# LCD.net
KiCad netlist of a schematic drawn in Altium Designer
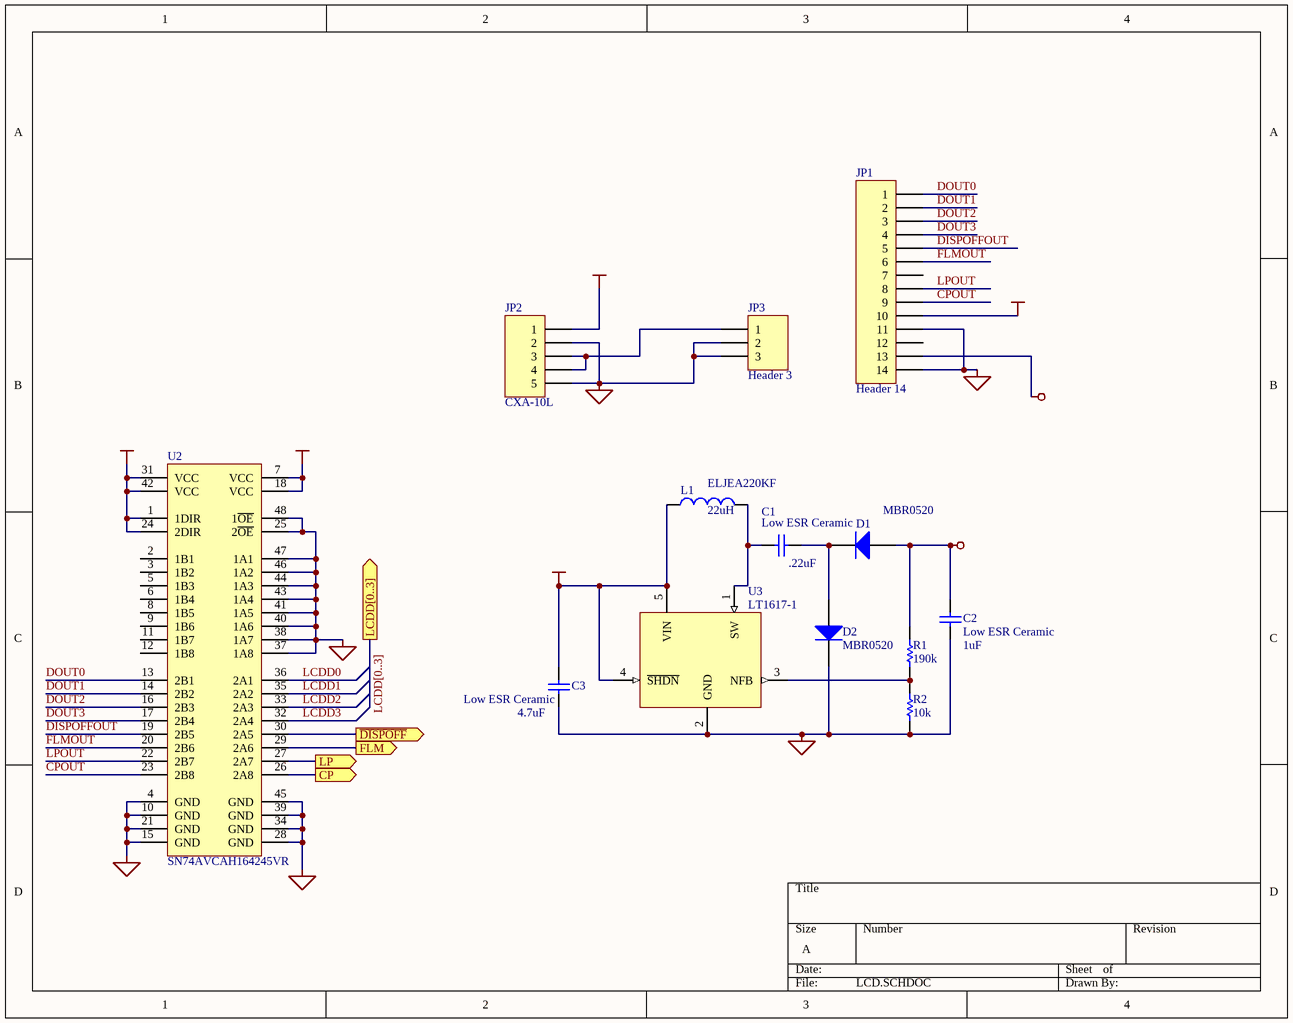
[diagram p0: LCD.SCHDOC]

(export (version "E")
  (design (tool "Eeschema 10.0.6"))
  (components
    (comp (ref "C1")
      (value "Low ESR Ceramic")
      (footprint "CC3216-1206")
      (description "Capacitor")
      (fields
        (field (name "MANUFACTURER") "Generic Components")
        (field (name "ALTIUM_VALUE") ".22uF")
        (field (name "PUBLISHER") "Altium Limited")
      )
      (libsource (lib "Miscellaneous Devices") (part "Cap"))
    )
    (comp (ref "C2")
      (value "Low ESR Ceramic")
      (footprint "CC3216-1206")
      (description "Capacitor")
      (fields
        (field (name "MANUFACTURER") "Generic Components")
        (field (name "ALTIUM_VALUE") "1uF")
        (field (name "PUBLISHER") "Altium Limited")
      )
      (libsource (lib "Miscellaneous Devices") (part "Cap"))
    )
    (comp (ref "C3")
      (value "Low ESR Ceramic")
      (footprint "CC3216-1206")
      (description "Capacitor")
      (fields
        (field (name "MANUFACTURER") "Generic Components")
        (field (name "ALTIUM_VALUE") "4.7uF")
        (field (name "PUBLISHER") "Altium Limited")
      )
      (libsource (lib "Miscellaneous Devices") (part "Cap"))
    )
    (comp (ref "D1")
      (value "MBR0520")
      (footprint "SOD-123")
      (description "Default Diode")
      (fields (field (name "MANUFACTURER") "Generic Components") (field (name "PUBLISHER") "Altium Limited"))
      (libsource (lib "Miscellaneous Devices") (part "Diode"))
    )
    (comp (ref "D2")
      (value "MBR0520")
      (footprint "SOD-123")
      (description "Default Diode")
      (fields (field (name "MANUFACTURER") "Generic Components") (field (name "PUBLISHER") "Altium Limited"))
      (libsource (lib "Miscellaneous Devices") (part "Diode"))
    )
    (comp (ref "JP1")
      (value "Header 14")
      (footprint "MOLEX FPC 14-CONN VERT")
      (description "Header, 14-Pin")
      (fields (field (name "MANUFACTURER") "Generic Components") (field (name "PUBLISHER") "Altium Limited"))
      (libsource (lib "Miscellaneous Connectors") (part "Header 14"))
    )
    (comp (ref "JP2")
      (value "CXA-10L")
      (footprint "CXA-L10L")
      (description "Header, 5-Pin")
      (fields (field (name "MANUFACTURER") "Generic Components") (field (name "PUBLISHER") "Altium Limited"))
      (libsource (lib "Miscellaneous Connectors") (part "Header 5"))
    )
    (comp (ref "JP3")
      (value "Header 3")
      (footprint "TERMBLOCK3.5x3")
      (description "Header, 3-Pin")
      (fields (field (name "MANUFACTURER") "Generic Components") (field (name "PUBLISHER") "Altium Limited"))
      (libsource (lib "Miscellaneous Connectors") (part "Header 3"))
    )
    (comp (ref "L1")
      (value "ELJEA220KF")
      (footprint "CC3225-1210")
      (description "Inductor")
      (fields
        (field (name "MANUFACTURER") "Generic Components")
        (field (name "ALTIUM_VALUE") "22uH")
        (field (name "PUBLISHER") "Altium Limited")
      )
      (libsource (lib "Miscellaneous Devices") (part "Inductor"))
    )
    (comp (ref "R1")
      (value "190k")
      (footprint "CC2012-0805")
      (description "Resistor")
      (fields
        (field (name "MANUFACTURER") "Generic Components")
        (field (name "Comment") "Res1")
        (field (name "PUBLISHER") "Altium Limited")
      )
      (libsource (lib "Miscellaneous Devices") (part "Res1"))
    )
    (comp (ref "R2")
      (value "10k")
      (footprint "CC2012-0805")
      (description "Resistor")
      (fields
        (field (name "MANUFACTURER") "Generic Components")
        (field (name "Comment") "Res1")
        (field (name "PUBLISHER") "Altium Limited")
      )
      (libsource (lib "Miscellaneous Devices") (part "Res1"))
    )
    (comp (ref "U2")
      (value "SN74AVCAH164245VR")
      (footprint "TSSO10x6-G48")
      (description "16-bit bus transceiver with 3-state outputs")
      (libsource (lib "My devices") (part "SN74LVCH16245A"))
    )
    (comp (ref "U3")
      (value "LT1617-1")
      (footprint "SO-G5/P.95")
      (description "Micropower Inverting DC/DC converter")
      (libsource (lib "My devices") (part "LT1617"))
    )
  )
  (nets
    (net (code "1") (name "+5VCC") (class "Default")
      (node (ref "JP1") (pin "10") (pinfunction "10_10") (pintype "passive"))
      (node (ref "JP2") (pin "1") (pinfunction "1_1") (pintype "passive"))
      (node (ref "U2") (pin "18") (pinfunction "VCC_18") (pintype "power_in"))
      (node (ref "U2") (pin "7") (pinfunction "VCC_7") (pintype "power_in"))
    )
    (net (code "2") (name "-25VEE") (class "Default")
      (node (ref "C2") (pin "2") (pinfunction "2_2") (pintype "passive"))
      (node (ref "D1") (pin "1") (pinfunction "A_1") (pintype "passive"))
      (node (ref "JP1") (pin "13") (pinfunction "13_13") (pintype "passive"))
      (node (ref "R1") (pin "2") (pinfunction "2_2") (pintype "passive"))
    )
    (net (code "3") (name "/CP") (class "Default")
      (node (ref "U2") (pin "26") (pinfunction "2A8_26") (pintype "passive"))
    )
    (net (code "4") (name "/CPOUT") (class "Default")
      (node (ref "JP1") (pin "9") (pinfunction "9_9") (pintype "passive"))
      (node (ref "U2") (pin "23") (pinfunction "2B8_23") (pintype "passive"))
    )
    (net (code "5") (name "/DISPOFFOUT") (class "Default")
      (node (ref "JP1") (pin "5") (pinfunction "5_5") (pintype "passive"))
      (node (ref "U2") (pin "19") (pinfunction "2B5_19") (pintype "passive"))
    )
    (net (code "6") (name "/DOUT0") (class "Default")
      (node (ref "JP1") (pin "1") (pinfunction "1_1") (pintype "passive"))
      (node (ref "U2") (pin "13") (pinfunction "2B1_13") (pintype "passive"))
    )
    (net (code "7") (name "/DOUT1") (class "Default")
      (node (ref "JP1") (pin "2") (pinfunction "2_2") (pintype "passive"))
      (node (ref "U2") (pin "14") (pinfunction "2B2_14") (pintype "passive"))
    )
    (net (code "8") (name "/DOUT2") (class "Default")
      (node (ref "JP1") (pin "3") (pinfunction "3_3") (pintype "passive"))
      (node (ref "U2") (pin "16") (pinfunction "2B3_16") (pintype "passive"))
    )
    (net (code "9") (name "/DOUT3") (class "Default")
      (node (ref "JP1") (pin "4") (pinfunction "4_4") (pintype "passive"))
      (node (ref "U2") (pin "17") (pinfunction "2B4_17") (pintype "passive"))
    )
    (net (code "10") (name "/FLM") (class "Default")
      (node (ref "U2") (pin "29") (pinfunction "2A6_29") (pintype "passive"))
    )
    (net (code "11") (name "/FLMOUT") (class "Default")
      (node (ref "JP1") (pin "6") (pinfunction "6_6") (pintype "passive"))
      (node (ref "U2") (pin "20") (pinfunction "2B6_20") (pintype "passive"))
    )
    (net (code "12") (name "/LCDD0") (class "Default")
      (node (ref "U2") (pin "36") (pinfunction "2A1_36") (pintype "passive"))
    )
    (net (code "13") (name "/LCDD1") (class "Default")
      (node (ref "U2") (pin "35") (pinfunction "2A2_35") (pintype "passive"))
    )
    (net (code "14") (name "/LCDD2") (class "Default")
      (node (ref "U2") (pin "33") (pinfunction "2A3_33") (pintype "passive"))
    )
    (net (code "15") (name "/LCDD3") (class "Default")
      (node (ref "U2") (pin "32") (pinfunction "2A4_32") (pintype "passive"))
    )
    (net (code "17") (name "/LP") (class "Default")
      (node (ref "U2") (pin "27") (pinfunction "2A7_27") (pintype "passive"))
    )
    (net (code "18") (name "/LPOUT") (class "Default")
      (node (ref "JP1") (pin "8") (pinfunction "8_8") (pintype "passive"))
      (node (ref "U2") (pin "22") (pinfunction "2B7_22") (pintype "passive"))
    )
    (net (code "19") (name "/~{DISPOFF}") (class "Default")
      (node (ref "U2") (pin "30") (pinfunction "2A5_30") (pintype "passive"))
    )
    (net (code "20") (name "GND") (class "Default")
      (node (ref "C2") (pin "1") (pinfunction "1_1") (pintype "passive"))
      (node (ref "C3") (pin "1") (pinfunction "1_1") (pintype "passive"))
      (node (ref "D2") (pin "2") (pinfunction "K_2") (pintype "passive"))
      (node (ref "JP1") (pin "11") (pinfunction "11_11") (pintype "passive"))
      (node (ref "JP1") (pin "14") (pinfunction "14_14") (pintype "passive"))
      (node (ref "JP2") (pin "2") (pinfunction "2_2") (pintype "passive"))
      (node (ref "JP2") (pin "5") (pinfunction "5_5") (pintype "passive"))
      (node (ref "JP3") (pin "2") (pinfunction "2_2") (pintype "passive"))
      (node (ref "JP3") (pin "3") (pinfunction "3_3") (pintype "passive"))
      (node (ref "R2") (pin "1") (pinfunction "1_1") (pintype "passive"))
      (node (ref "U2") (pin "10") (pinfunction "GND_10") (pintype "power_in"))
      (node (ref "U2") (pin "15") (pinfunction "GND_15") (pintype "power_in"))
      (node (ref "U2") (pin "21") (pinfunction "GND_21") (pintype "power_in"))
      (node (ref "U2") (pin "25") (pinfunction "2~{OE}_25") (pintype "passive"))
      (node (ref "U2") (pin "28") (pinfunction "GND_28") (pintype "power_in"))
      (node (ref "U2") (pin "34") (pinfunction "GND_34") (pintype "power_in"))
      (node (ref "U2") (pin "37") (pinfunction "1A8_37") (pintype "passive"))
      (node (ref "U2") (pin "38") (pinfunction "1A7_38") (pintype "passive"))
      (node (ref "U2") (pin "39") (pinfunction "GND_39") (pintype "power_in"))
      (node (ref "U2") (pin "4") (pinfunction "GND_4") (pintype "power_in"))
      (node (ref "U2") (pin "40") (pinfunction "1A6_40") (pintype "passive"))
      (node (ref "U2") (pin "41") (pinfunction "1A5_41") (pintype "passive"))
      (node (ref "U2") (pin "43") (pinfunction "1A4_43") (pintype "passive"))
      (node (ref "U2") (pin "44") (pinfunction "1A3_44") (pintype "passive"))
      (node (ref "U2") (pin "45") (pinfunction "GND_45") (pintype "power_in"))
      (node (ref "U2") (pin "46") (pinfunction "1A2_46") (pintype "passive"))
      (node (ref "U2") (pin "47") (pinfunction "1A1_47") (pintype "passive"))
      (node (ref "U2") (pin "48") (pinfunction "1~{OE}_48") (pintype "passive"))
      (node (ref "U3") (pin "2") (pinfunction "GND_2") (pintype "power_in"))
    )
    (net (code "21") (name "Net-(D1-K)") (class "Default")
      (node (ref "C1") (pin "1") (pinfunction "1_1") (pintype "passive"))
      (node (ref "D1") (pin "2") (pinfunction "K_2") (pintype "passive"))
      (node (ref "D2") (pin "1") (pinfunction "A_1") (pintype "passive"))
    )
    (net (code "22") (name "Net-(JP2-Pad3)") (class "Default")
      (node (ref "JP2") (pin "3") (pinfunction "3_3") (pintype "passive"))
      (node (ref "JP2") (pin "4") (pinfunction "4_4") (pintype "passive"))
      (node (ref "JP3") (pin "1") (pinfunction "1_1") (pintype "passive"))
    )
    (net (code "23") (name "Net-(U3-NFB)") (class "Default")
      (node (ref "R1") (pin "1") (pinfunction "1_1") (pintype "passive"))
      (node (ref "R2") (pin "2") (pinfunction "2_2") (pintype "passive"))
      (node (ref "U3") (pin "3") (pinfunction "NFB_3") (pintype "output"))
    )
    (net (code "24") (name "Net-(U3-SW)") (class "Default")
      (node (ref "C1") (pin "2") (pinfunction "2_2") (pintype "passive"))
      (node (ref "L1") (pin "2") (pinfunction "2_2") (pintype "passive"))
      (node (ref "U3") (pin "1") (pinfunction "SW_1") (pintype "input"))
    )
    (net (code "25") (name "VCC") (class "Default")
      (node (ref "C3") (pin "2") (pinfunction "2_2") (pintype "passive"))
      (node (ref "L1") (pin "1") (pinfunction "1_1") (pintype "passive"))
      (node (ref "U2") (pin "1") (pinfunction "1DIR_1") (pintype "passive"))
      (node (ref "U2") (pin "24") (pinfunction "2DIR_24") (pintype "passive"))
      (node (ref "U2") (pin "31") (pinfunction "VCC_31") (pintype "power_in"))
      (node (ref "U2") (pin "42") (pinfunction "VCC_42") (pintype "power_in"))
      (node (ref "U3") (pin "4") (pinfunction "~{SHDN}_4") (pintype "input"))
      (node (ref "U3") (pin "5") (pinfunction "VIN_5") (pintype "power_in"))
    )
    (net (code "26") (name "unconnected-(JP1-Pad7)") (class "Default")
      (node (ref "JP1") (pin "7") (pinfunction "7_7") (pintype "passive"))
    )
    (net (code "27") (name "unconnected-(JP1-Pad12)") (class "Default")
      (node (ref "JP1") (pin "12") (pinfunction "12_12") (pintype "passive"))
    )
    (net (code "28") (name "unconnected-(U2-1B1-Pad2)") (class "Default")
      (node (ref "U2") (pin "2") (pinfunction "1B1_2") (pintype "passive"))
    )
    (net (code "29") (name "unconnected-(U2-1B2-Pad3)") (class "Default")
      (node (ref "U2") (pin "3") (pinfunction "1B2_3") (pintype "passive"))
    )
    (net (code "30") (name "unconnected-(U2-1B3-Pad5)") (class "Default")
      (node (ref "U2") (pin "5") (pinfunction "1B3_5") (pintype "passive"))
    )
    (net (code "31") (name "unconnected-(U2-1B4-Pad6)") (class "Default")
      (node (ref "U2") (pin "6") (pinfunction "1B4_6") (pintype "passive"))
    )
    (net (code "32") (name "unconnected-(U2-1B5-Pad8)") (class "Default")
      (node (ref "U2") (pin "8") (pinfunction "1B5_8") (pintype "passive"))
    )
    (net (code "33") (name "unconnected-(U2-1B6-Pad9)") (class "Default")
      (node (ref "U2") (pin "9") (pinfunction "1B6_9") (pintype "passive"))
    )
    (net (code "34") (name "unconnected-(U2-1B7-Pad11)") (class "Default")
      (node (ref "U2") (pin "11") (pinfunction "1B7_11") (pintype "passive"))
    )
    (net (code "35") (name "unconnected-(U2-1B8-Pad12)") (class "Default")
      (node (ref "U2") (pin "12") (pinfunction "1B8_12") (pintype "passive"))
    )
  )
)
